# Connectors.net
KiCad netlist of a schematic drawn in Altium Designer
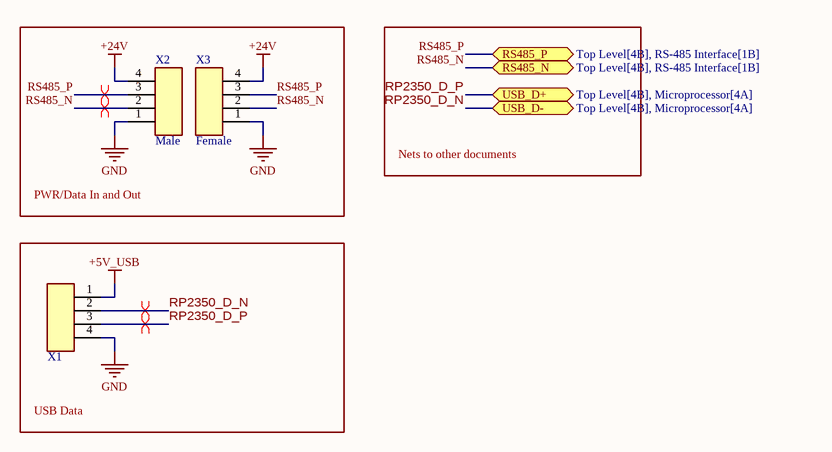
[diagram p0: Connectors.SchDoc]

(export (version "E")
  (design (tool "Eeschema 10.0.6"))
  (components
    (comp (ref "X1")
      (value "[Sherlock] 4pin")
      (footprint "[Sherlock] 4pin")
      (description "0353620450")
      (libsource (lib "Connectors") (part "[Sherlock] 4pin"))
    )
    (comp (ref "X2")
      (value "Male")
      (footprint "[Pogo] Magnetic Right-Angle 4pos Male")
      (description "5358")
      (libsource (lib "Connectors") (part "[Pogo] Magnetic Right-Angle 4pos Male"))
    )
    (comp (ref "X3")
      (value "Female")
      (footprint "[Pogo] Magnetic Right-Angle 4pos Female")
      (description "5358")
      (libsource (lib "Connectors") (part "[Pogo] Magnetic Right-Angle 4pos Female"))
    )
  )
  (nets
    (net (code "1") (name "+5V_USB") (class "Default") (node (ref "X1") (pin "1") (pintype "passive")))
    (net (code "2") (name "+24V") (class "Default")
      (node (ref "X2") (pin "4") (pintype "passive"))
      (node (ref "X3") (pin "4") (pintype "passive"))
    )
    (net (code "3") (name "/RP2350_D_N") (class "Default") (node (ref "X1") (pin "2") (pintype "passive")))
    (net (code "4") (name "/RP2350_D_P") (class "Default") (node (ref "X1") (pin "3") (pintype "passive")))
    (net (code "5") (name "/RS485_N") (class "Default")
      (node (ref "X2") (pin "2") (pintype "passive"))
      (node (ref "X3") (pin "2") (pintype "passive"))
    )
    (net (code "6") (name "/RS485_P") (class "Default")
      (node (ref "X2") (pin "3") (pintype "passive"))
      (node (ref "X3") (pin "3") (pintype "passive"))
    )
    (net (code "7") (name "GND") (class "Default")
      (node (ref "X1") (pin "4") (pintype "passive"))
      (node (ref "X2") (pin "1") (pintype "passive"))
      (node (ref "X3") (pin "1") (pintype "passive"))
    )
  )
)
